# midi_out.net
KiCad netlist of a schematic drawn in EAGLE
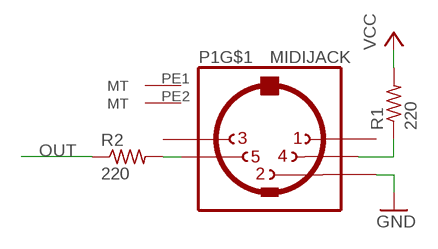
[diagram p0: schematic, sheet 1]

(export (version "E")
  (design (tool "Eeschema 10.0.6"))
  (components
    (comp (ref "P1")
      (value "MIDIJACK")
      (footprint "eagle-import:CP-2350")
      (libsource (lib "eagle-import") (part "MIDIJACK"))
    )
    (comp (ref "R1")
      (value "220")
      (footprint "eagle-import:0204_5")
      (libsource (lib "eagle-import") (part "R-US_0204/5"))
    )
    (comp (ref "R2")
      (value "220")
      (footprint "eagle-import:0204_5")
      (libsource (lib "eagle-import") (part "R-US_0204/5"))
    )
  )
  (nets
    (net (code "1") (name "/OUT") (class "Default")
      (node (ref "R2") (pin "1") (pinfunction "1_1") (pintype "passive"))
    )
    (net (code "2") (name "GND") (class "Default")
      (node (ref "P1") (pin "2") (pinfunction "2_2") (pintype "passive"))
    )
    (net (code "3") (name "Net-(P1-Pad4)") (class "Default")
      (node (ref "P1") (pin "4") (pinfunction "4_4") (pintype "passive"))
      (node (ref "R1") (pin "1") (pinfunction "1_1") (pintype "passive"))
    )
    (net (code "4") (name "Net-(P1-Pad5)") (class "Default")
      (node (ref "P1") (pin "5") (pinfunction "5_5") (pintype "passive"))
      (node (ref "R2") (pin "2") (pinfunction "2_2") (pintype "passive"))
    )
    (net (code "5") (name "VCC") (class "Default")
      (node (ref "R1") (pin "2") (pinfunction "2_2") (pintype "passive"))
    )
    (net (code "6") (name "unconnected-(P1-Pad1)") (class "Default")
      (node (ref "P1") (pin "1") (pinfunction "1_1") (pintype "passive"))
    )
    (net (code "7") (name "unconnected-(P1-Pad3)") (class "Default")
      (node (ref "P1") (pin "3") (pinfunction "3_3") (pintype "passive"))
    )
    (net (code "8") (name "unconnected-(P1D-MT-PadPE1)") (class "Default")
      (node (ref "P1") (pin "PE1") (pinfunction "MT_PE1") (pintype "passive"))
    )
    (net (code "9") (name "unconnected-(P1E-MT-PadPE2)") (class "Default")
      (node (ref "P1") (pin "PE2") (pinfunction "MT_PE2") (pintype "passive"))
    )
  )
)
